# Line.net
KiCad netlist of a schematic drawn in Altium Designer
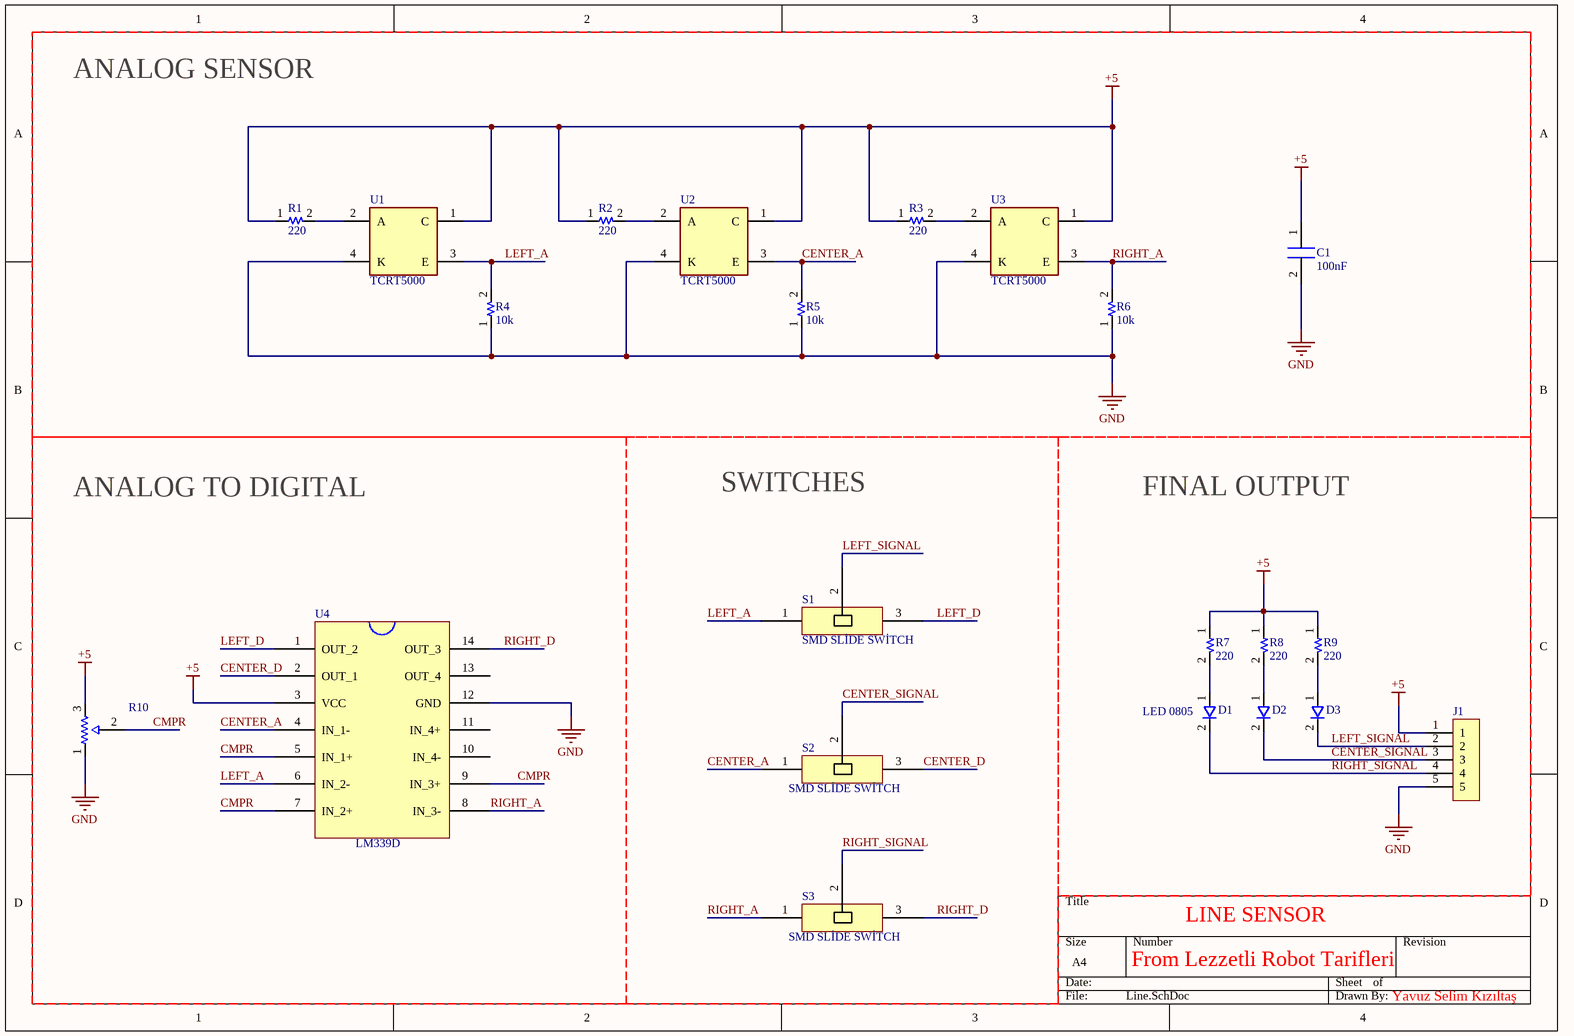
[diagram p0: Line.SchDoc]

(export (version "E")
  (design (tool "Eeschema 10.0.6"))
  (components
    (comp (ref "C1") (value "100nF") (footprint "C0805") (libsource (lib "Line") (part "C0805")))
    (comp (ref "D1") (value "LED 0805") (footprint "LED 0805") (libsource (lib "Line") (part "LED 0805")))
    (comp (ref "D2") (value "LED 0805") (footprint "LED 0805") (libsource (lib "Line") (part "LED 0805")))
    (comp (ref "D3") (value "LED 0805") (footprint "LED 0805") (libsource (lib "Line") (part "LED 0805")))
    (comp (ref "J1")
      (value "1x5 MALE HEADER")
      (footprint "1x5 MALE HEADER")
      (libsource (lib "Line") (part "1x5 MALE HEADER"))
    )
    (comp (ref "R1")
      (value "220")
      (footprint "R0805 Resistor")
      (libsource (lib "Line") (part "R0805 Resistor"))
    )
    (comp (ref "R2")
      (value "220")
      (footprint "R0805 Resistor")
      (libsource (lib "Line") (part "R0805 Resistor"))
    )
    (comp (ref "R3")
      (value "220")
      (footprint "R0805 Resistor")
      (libsource (lib "Line") (part "R0805 Resistor"))
    )
    (comp (ref "R4")
      (value "10k")
      (footprint "R0805 Resistor")
      (libsource (lib "Line") (part "R0805 Resistor"))
    )
    (comp (ref "R5")
      (value "10k")
      (footprint "R0805 Resistor")
      (libsource (lib "Line") (part "R0805 Resistor"))
    )
    (comp (ref "R6")
      (value "10k")
      (footprint "R0805 Resistor")
      (libsource (lib "Line") (part "R0805 Resistor"))
    )
    (comp (ref "R7")
      (value "220")
      (footprint "R0805 Resistor")
      (libsource (lib "Line") (part "R0805 Resistor"))
    )
    (comp (ref "R8")
      (value "220")
      (footprint "R0805 Resistor")
      (libsource (lib "Line") (part "R0805 Resistor"))
    )
    (comp (ref "R9")
      (value "220")
      (footprint "R0805 Resistor")
      (libsource (lib "Line") (part "R0805 Resistor"))
    )
    (comp (ref "R10")
      (value "TRIMPOT 5mm")
      (footprint "TRIMPOT 5mm")
      (description "TS53 TRIMPOT SMD 5mm")
      (libsource (lib "Line") (part "TRIMPOT 5mm"))
    )
    (comp (ref "S1")
      (value "SMD SLİDE SWİTCH")
      (footprint "SMD Slide Switch")
      (libsource (lib "Line") (part "SMD SLİDE SWİTCH"))
    )
    (comp (ref "S2")
      (value "SMD SLİDE SWİTCH")
      (footprint "SMD Slide Switch")
      (libsource (lib "Line") (part "SMD SLİDE SWİTCH"))
    )
    (comp (ref "S3")
      (value "SMD SLİDE SWİTCH")
      (footprint "SMD Slide Switch")
      (libsource (lib "Line") (part "SMD SLİDE SWİTCH"))
    )
    (comp (ref "U1")
      (value "TCRT5000")
      (footprint "TCRT5000")
      (description "TCRT5000 Kızıl Ötesi Sensör")
      (fields
        (field (name "MANUFACTURER") "Vishay")
        (field (name "MOUSER PART NUMBER") "782-TCRT5000")
        (field (name "PART NUMBER") "TCRT5000")
      )
      (libsource (lib "Line") (part "TCRT5000"))
    )
    (comp (ref "U2")
      (value "TCRT5000")
      (footprint "TCRT5000")
      (description "TCRT5000 Kızıl Ötesi Sensör")
      (fields
        (field (name "MANUFACTURER") "Vishay")
        (field (name "MOUSER PART NUMBER") "782-TCRT5000")
        (field (name "PART NUMBER") "TCRT5000")
      )
      (libsource (lib "Line") (part "TCRT5000"))
    )
    (comp (ref "U3")
      (value "TCRT5000")
      (footprint "TCRT5000")
      (description "TCRT5000 Kızıl Ötesi Sensör")
      (fields
        (field (name "MANUFACTURER") "Vishay")
        (field (name "MOUSER PART NUMBER") "782-TCRT5000")
        (field (name "PART NUMBER") "TCRT5000")
      )
      (libsource (lib "Line") (part "TCRT5000"))
    )
    (comp (ref "U4")
      (value "LM339D")
      (footprint "LM339D")
      (description "LM33D Voltage Comparator")
      (libsource (lib "Line") (part "LM339D"))
    )
  )
  (nets
    (net (code "1") (name "+5") (class "Default")
      (node (ref "C1") (pin "1") (pinfunction "1_1") (pintype "passive"))
      (node (ref "J1") (pin "1") (pinfunction "1_1") (pintype "passive"))
      (node (ref "R1") (pin "1") (pinfunction "1_1") (pintype "passive"))
      (node (ref "R10") (pin "3") (pinfunction "2_3") (pintype "passive"))
      (node (ref "R2") (pin "1") (pinfunction "1_1") (pintype "passive"))
      (node (ref "R3") (pin "1") (pinfunction "1_1") (pintype "passive"))
      (node (ref "R7") (pin "1") (pinfunction "1_1") (pintype "passive"))
      (node (ref "R8") (pin "1") (pinfunction "1_1") (pintype "passive"))
      (node (ref "R9") (pin "1") (pinfunction "1_1") (pintype "passive"))
      (node (ref "U1") (pin "1") (pinfunction "C_1") (pintype "passive"))
      (node (ref "U2") (pin "1") (pinfunction "C_1") (pintype "passive"))
      (node (ref "U3") (pin "1") (pinfunction "C_1") (pintype "passive"))
      (node (ref "U4") (pin "3") (pinfunction "VCC_3") (pintype "passive"))
    )
    (net (code "2") (name "/CENTER_A") (class "Default")
      (node (ref "R5") (pin "2") (pinfunction "2_2") (pintype "passive"))
      (node (ref "S2") (pin "1") (pinfunction "VSS_1") (pintype "passive"))
      (node (ref "U2") (pin "3") (pinfunction "E_3") (pintype "passive"))
      (node (ref "U4") (pin "4") (pinfunction "IN_1-_4") (pintype "passive"))
    )
    (net (code "3") (name "/CENTER_D") (class "Default")
      (node (ref "S2") (pin "3") (pinfunction "VSS_3") (pintype "passive"))
      (node (ref "U4") (pin "2") (pinfunction "OUT_1_2") (pintype "passive"))
    )
    (net (code "4") (name "/CENTER_SIGNAL") (class "Default")
      (node (ref "D2") (pin "2") (pintype "passive"))
      (node (ref "J1") (pin "3") (pinfunction "3_3") (pintype "passive"))
      (node (ref "S2") (pin "2") (pinfunction "VSS_2") (pintype "passive"))
    )
    (net (code "5") (name "/CMPR") (class "Default")
      (node (ref "R10") (pin "2") (pinfunction "3_2") (pintype "passive"))
      (node (ref "U4") (pin "5") (pinfunction "IN_1+_5") (pintype "passive"))
      (node (ref "U4") (pin "7") (pinfunction "IN_2+_7") (pintype "passive"))
      (node (ref "U4") (pin "9") (pinfunction "IN_3+_9") (pintype "passive"))
    )
    (net (code "6") (name "/LEFT_A") (class "Default")
      (node (ref "R4") (pin "2") (pinfunction "2_2") (pintype "passive"))
      (node (ref "S1") (pin "1") (pinfunction "VSS_1") (pintype "passive"))
      (node (ref "U1") (pin "3") (pinfunction "E_3") (pintype "passive"))
      (node (ref "U4") (pin "6") (pinfunction "IN_2-_6") (pintype "passive"))
    )
    (net (code "7") (name "/LEFT_D") (class "Default")
      (node (ref "S1") (pin "3") (pinfunction "VSS_3") (pintype "passive"))
      (node (ref "U4") (pin "1") (pinfunction "OUT_2_1") (pintype "passive"))
    )
    (net (code "8") (name "/LEFT_SIGNAL") (class "Default")
      (node (ref "D3") (pin "2") (pintype "passive"))
      (node (ref "J1") (pin "2") (pinfunction "2_2") (pintype "passive"))
      (node (ref "S1") (pin "2") (pinfunction "VSS_2") (pintype "passive"))
    )
    (net (code "9") (name "/RIGHT_A") (class "Default")
      (node (ref "R6") (pin "2") (pinfunction "2_2") (pintype "passive"))
      (node (ref "S3") (pin "1") (pinfunction "VSS_1") (pintype "passive"))
      (node (ref "U3") (pin "3") (pinfunction "E_3") (pintype "passive"))
      (node (ref "U4") (pin "8") (pinfunction "IN_3-_8") (pintype "passive"))
    )
    (net (code "10") (name "/RIGHT_D") (class "Default")
      (node (ref "S3") (pin "3") (pinfunction "VSS_3") (pintype "passive"))
      (node (ref "U4") (pin "14") (pinfunction "OUT_3_14") (pintype "passive"))
    )
    (net (code "11") (name "/RIGHT_SIGNAL") (class "Default")
      (node (ref "D1") (pin "2") (pintype "passive"))
      (node (ref "J1") (pin "4") (pinfunction "4_4") (pintype "passive"))
      (node (ref "S3") (pin "2") (pinfunction "VSS_2") (pintype "passive"))
    )
    (net (code "12") (name "GND") (class "Default")
      (node (ref "C1") (pin "2") (pinfunction "2_2") (pintype "passive"))
      (node (ref "J1") (pin "5") (pinfunction "5_5") (pintype "passive"))
      (node (ref "R10") (pin "1") (pinfunction "1_1") (pintype "passive"))
      (node (ref "R4") (pin "1") (pinfunction "1_1") (pintype "passive"))
      (node (ref "R5") (pin "1") (pinfunction "1_1") (pintype "passive"))
      (node (ref "R6") (pin "1") (pinfunction "1_1") (pintype "passive"))
      (node (ref "U1") (pin "4") (pinfunction "K_4") (pintype "passive"))
      (node (ref "U2") (pin "4") (pinfunction "K_4") (pintype "passive"))
      (node (ref "U3") (pin "4") (pinfunction "K_4") (pintype "passive"))
      (node (ref "U4") (pin "12") (pinfunction "GND_12") (pintype "passive"))
    )
    (net (code "13") (name "Net-(D1-Pad1)") (class "Default")
      (node (ref "D1") (pin "1") (pintype "passive"))
      (node (ref "R7") (pin "2") (pinfunction "2_2") (pintype "passive"))
    )
    (net (code "14") (name "Net-(D2-Pad1)") (class "Default")
      (node (ref "D2") (pin "1") (pintype "passive"))
      (node (ref "R8") (pin "2") (pinfunction "2_2") (pintype "passive"))
    )
    (net (code "15") (name "Net-(D3-Pad1)") (class "Default")
      (node (ref "D3") (pin "1") (pintype "passive"))
      (node (ref "R9") (pin "2") (pinfunction "2_2") (pintype "passive"))
    )
    (net (code "16") (name "Net-(U1-A)") (class "Default")
      (node (ref "R1") (pin "2") (pinfunction "2_2") (pintype "passive"))
      (node (ref "U1") (pin "2") (pinfunction "A_2") (pintype "passive"))
    )
    (net (code "17") (name "Net-(U2-A)") (class "Default")
      (node (ref "R2") (pin "2") (pinfunction "2_2") (pintype "passive"))
      (node (ref "U2") (pin "2") (pinfunction "A_2") (pintype "passive"))
    )
    (net (code "18") (name "Net-(U3-A)") (class "Default")
      (node (ref "R3") (pin "2") (pinfunction "2_2") (pintype "passive"))
      (node (ref "U3") (pin "2") (pinfunction "A_2") (pintype "passive"))
    )
    (net (code "19") (name "unconnected-(U4-IN_4+-Pad11)") (class "Default")
      (node (ref "U4") (pin "11") (pinfunction "IN_4+_11") (pintype "passive"))
    )
    (net (code "20") (name "unconnected-(U4-IN_4--Pad10)") (class "Default")
      (node (ref "U4") (pin "10") (pinfunction "IN_4-_10") (pintype "passive"))
    )
    (net (code "21") (name "unconnected-(U4-OUT_4-Pad13)") (class "Default")
      (node (ref "U4") (pin "13") (pinfunction "OUT_4_13") (pintype "passive"))
    )
  )
)
